# T-LOG_v1_1.net
KiCad netlist of a schematic drawn in Altium Designer
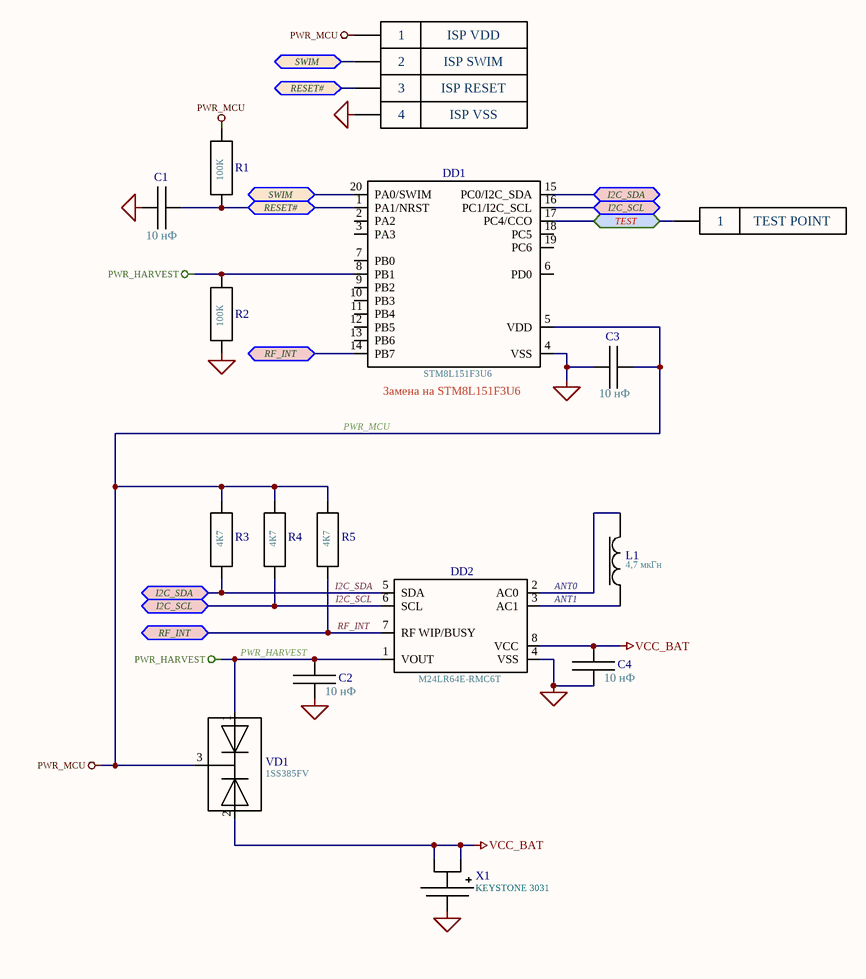
[diagram p0: T-LOG v1.1.SchDoc]

(export (version "E")
  (design (tool "Eeschema 10.0.6"))
  (components
    (comp (ref "C1")
      (value "10 нФ")
      (footprint "C0402")
      (description "Чип-конденсатор 0,01 мкФ 50 В 0402")
      (libsource (lib "RC") (part "C0402"))
    )
    (comp (ref "C2")
      (value "10 нФ")
      (footprint "C0402")
      (description "Чип-конденсатор 0,01 мкФ 50 В 0402")
      (libsource (lib "RC") (part "C0402"))
    )
    (comp (ref "C3")
      (value "10 нФ")
      (footprint "C0402")
      (description "Чип-конденсатор 0,01 мкФ 50 В 0402")
      (libsource (lib "RC") (part "C0402"))
    )
    (comp (ref "C4")
      (value "10 нФ")
      (footprint "C0402")
      (description "Чип-конденсатор 0,01 мкФ 50 В 0402")
      (libsource (lib "RC") (part "C0402"))
    )
    (comp (ref "DD1")
      (value "STM8L151F3U6")
      (footprint "UFQPN20_3x3_0.5")
      (description "Микроконтроллер  STM8L151F3U6 UFQFPN-20")
      (libsource (lib "MCU") (part "STM8L151F3U6"))
    )
    (comp (ref "DD2")
      (value "M24LR64E-RMC6T")
      (footprint "UDFN-8_2X3")
      (description "Память EEPROM I2C/NFC 64Кбит M24LR64E-RMC6T UFDFN8 ST")
      (libsource (lib "MEMORY") (part "M24LR64E-RMC6T"))
    )
    (comp (ref "K1")
      (value "ISP")
      (footprint "THRU_HOLE_02x045")
      (description "used for STM8L ISP in T-LOG project")
      (libsource (lib "CONNECTORS") (part "THRU_HOLE_02x045"))
    )
    (comp (ref "K2")
      (value "ISP")
      (footprint "THRU_HOLE_02x045")
      (description "used for STM8L ISP in T-LOG project")
      (libsource (lib "CONNECTORS") (part "THRU_HOLE_02x045"))
    )
    (comp (ref "K3")
      (value "ISP")
      (footprint "THRU_HOLE_02x045")
      (description "used for STM8L ISP in T-LOG project")
      (libsource (lib "CONNECTORS") (part "THRU_HOLE_02x045"))
    )
    (comp (ref "K4")
      (value "ISP")
      (footprint "THRU_HOLE_02x045")
      (description "used for STM8L ISP in T-LOG project")
      (libsource (lib "CONNECTORS") (part "THRU_HOLE_02x045"))
    )
    (comp (ref "K5")
      (value "TEST POINT")
      (footprint "THRU_HOLE_02x045")
      (libsource (lib "CONNECTORS") (part "THRU_HOLE_02x045"))
    )
    (comp (ref "L1")
      (value "4,7 мкГн")
      (footprint "WE-LQ_1210")
      (description "Чип-индуктивность WE-LQ 744032004 4,7 мкГн 0,49 А Wurth Elektronik")
      (libsource (lib "ZX") (part "WE-LQ_744032004"))
    )
    (comp (ref "R1")
      (value "100К")
      (footprint "R0402")
      (description "Чип-резистор 100 кОм 5% 0402")
      (libsource (lib "RC") (part "R0402"))
    )
    (comp (ref "R2")
      (value "100К")
      (footprint "R0402")
      (description "Чип-резистор 100 кОм 5% 0402")
      (libsource (lib "RC") (part "R0402"))
    )
    (comp (ref "R3")
      (value "4К7")
      (footprint "R0402")
      (description "Чип-резистор 4,7 кОм 5% 0402")
      (libsource (lib "RC") (part "R0402"))
    )
    (comp (ref "R4")
      (value "4К7")
      (footprint "R0402")
      (description "Чип-резистор 4,7 кОм 5% 0402")
      (libsource (lib "RC") (part "R0402"))
    )
    (comp (ref "R5")
      (value "4К7")
      (footprint "R0402")
      (description "Чип-резистор 4,7 кОм 5% 0402")
      (libsource (lib "RC") (part "R0402"))
    )
    (comp (ref "VD1")
      (value "1SS385FV")
      (footprint "SOT-723")
      (description "Диодная сборка с общим катодом 1SS385FV SOT-723 Toshiba")
      (libsource (lib "SEMICONDUCTORS") (part "1SS385FV"))
    )
    (comp (ref "X1")
      (value "KEYSTONE 3031")
      (footprint "KEYSTONE_3031")
      (description "Держатель элемента CR1025 KEYSTONE 3031")
      (libsource (lib "CONNECTORS") (part "KEYSTONE_3031"))
    )
  )
  (nets
    (net (code "1") (name "/ANT0") (class "Default")
      (node (ref "DD2") (pin "2") (pinfunction "AC0_2") (pintype "passive"))
      (node (ref "L1") (pin "2") (pinfunction "2_2") (pintype "passive"))
    )
    (net (code "2") (name "/ANT1") (class "Default")
      (node (ref "DD2") (pin "3") (pinfunction "AC1_3") (pintype "passive"))
      (node (ref "L1") (pin "1") (pinfunction "1_1") (pintype "passive"))
    )
    (net (code "3") (name "/I2C_SCL") (class "Default")
      (node (ref "DD1") (pin "16") (pinfunction "PC1/I2C_SCL_16") (pintype "passive"))
      (node (ref "DD2") (pin "6") (pinfunction "SCL_6") (pintype "passive"))
      (node (ref "R4") (pin "1") (pinfunction "1_1") (pintype "passive"))
    )
    (net (code "4") (name "/I2C_SDA") (class "Default")
      (node (ref "DD1") (pin "15") (pinfunction "PC0/I2C_SDA_15") (pintype "passive"))
      (node (ref "DD2") (pin "5") (pinfunction "SDA_5") (pintype "passive"))
      (node (ref "R3") (pin "1") (pinfunction "1_1") (pintype "passive"))
    )
    (net (code "5") (name "/RESET#") (class "Default")
      (node (ref "C1") (pin "2") (pinfunction "2_2") (pintype "passive"))
      (node (ref "DD1") (pin "1") (pinfunction "PA1/NRST_1") (pintype "passive"))
      (node (ref "K3") (pin "1") (pinfunction "1_1") (pintype "passive"))
      (node (ref "R1") (pin "1") (pinfunction "1_1") (pintype "passive"))
    )
    (net (code "6") (name "/RF_INT") (class "Default")
      (node (ref "DD1") (pin "14") (pinfunction "PB7_14") (pintype "passive"))
      (node (ref "DD2") (pin "7") (pinfunction "RF_WIP/BUSY_7") (pintype "passive"))
      (node (ref "R5") (pin "1") (pinfunction "1_1") (pintype "passive"))
    )
    (net (code "7") (name "/SWIM") (class "Default")
      (node (ref "DD1") (pin "20") (pinfunction "PA0/SWIM_20") (pintype "passive"))
      (node (ref "K2") (pin "1") (pinfunction "1_1") (pintype "passive"))
    )
    (net (code "8") (name "/TEST") (class "Default")
      (node (ref "DD1") (pin "17") (pinfunction "PC4/CCO_17") (pintype "passive"))
      (node (ref "K5") (pin "1") (pinfunction "1_1") (pintype "passive"))
    )
    (net (code "9") (name "GND") (class "Default")
      (node (ref "C1") (pin "1") (pinfunction "1_1") (pintype "passive"))
      (node (ref "C2") (pin "1") (pinfunction "1_1") (pintype "passive"))
      (node (ref "C3") (pin "2") (pinfunction "2_2") (pintype "passive"))
      (node (ref "C4") (pin "1") (pinfunction "1_1") (pintype "passive"))
      (node (ref "DD1") (pin "4") (pinfunction "VSS_4") (pintype "passive"))
      (node (ref "DD2") (pin "4") (pinfunction "VSS_4") (pintype "passive"))
      (node (ref "K4") (pin "1") (pinfunction "1_1") (pintype "passive"))
      (node (ref "R2") (pin "1") (pinfunction "1_1") (pintype "passive"))
      (node (ref "X1") (pin "3") (pinfunction "3_3") (pintype "passive"))
    )
    (net (code "10") (name "PWR_HARVEST") (class "Default")
      (node (ref "C2") (pin "2") (pinfunction "2_2") (pintype "passive"))
      (node (ref "DD1") (pin "8") (pinfunction "PB1_8") (pintype "passive"))
      (node (ref "DD2") (pin "1") (pinfunction "VOUT_1") (pintype "passive"))
      (node (ref "R2") (pin "2") (pinfunction "2_2") (pintype "passive"))
      (node (ref "VD1") (pin "1") (pinfunction "1_1") (pintype "passive"))
    )
    (net (code "11") (name "PWR_MCU") (class "Default")
      (node (ref "C3") (pin "1") (pinfunction "1_1") (pintype "passive"))
      (node (ref "DD1") (pin "5") (pinfunction "VDD_5") (pintype "passive"))
      (node (ref "K1") (pin "1") (pinfunction "1_1") (pintype "passive"))
      (node (ref "R1") (pin "2") (pinfunction "2_2") (pintype "passive"))
      (node (ref "R3") (pin "2") (pinfunction "2_2") (pintype "passive"))
      (node (ref "R4") (pin "2") (pinfunction "2_2") (pintype "passive"))
      (node (ref "R5") (pin "2") (pinfunction "2_2") (pintype "passive"))
      (node (ref "VD1") (pin "3") (pinfunction "3_3") (pintype "passive"))
    )
    (net (code "12") (name "VCC_BAT") (class "Default")
      (node (ref "C4") (pin "2") (pinfunction "2_2") (pintype "passive"))
      (node (ref "DD2") (pin "8") (pinfunction "VCC_8") (pintype "passive"))
      (node (ref "VD1") (pin "2") (pinfunction "2_2") (pintype "passive"))
      (node (ref "X1") (pin "1") (pinfunction "1_1") (pintype "passive"))
      (node (ref "X1") (pin "2") (pinfunction "2_2") (pintype "passive"))
    )
    (net (code "13") (name "unconnected-(DD1-PA2-Pad2)") (class "Default")
      (node (ref "DD1") (pin "2") (pinfunction "PA2_2") (pintype "passive"))
    )
    (net (code "14") (name "unconnected-(DD1-PA3-Pad3)") (class "Default")
      (node (ref "DD1") (pin "3") (pinfunction "PA3_3") (pintype "passive"))
    )
    (net (code "15") (name "unconnected-(DD1-PB0-Pad7)") (class "Default")
      (node (ref "DD1") (pin "7") (pinfunction "PB0_7") (pintype "passive"))
    )
    (net (code "16") (name "unconnected-(DD1-PB2-Pad9)") (class "Default")
      (node (ref "DD1") (pin "9") (pinfunction "PB2_9") (pintype "passive"))
    )
    (net (code "17") (name "unconnected-(DD1-PB3-Pad10)") (class "Default")
      (node (ref "DD1") (pin "10") (pinfunction "PB3_10") (pintype "passive"))
    )
    (net (code "18") (name "unconnected-(DD1-PB4-Pad11)") (class "Default")
      (node (ref "DD1") (pin "11") (pinfunction "PB4_11") (pintype "passive"))
    )
    (net (code "19") (name "unconnected-(DD1-PB5-Pad12)") (class "Default")
      (node (ref "DD1") (pin "12") (pinfunction "PB5_12") (pintype "passive"))
    )
    (net (code "20") (name "unconnected-(DD1-PB6-Pad13)") (class "Default")
      (node (ref "DD1") (pin "13") (pinfunction "PB6_13") (pintype "passive"))
    )
    (net (code "21") (name "unconnected-(DD1-PC5-Pad18)") (class "Default")
      (node (ref "DD1") (pin "18") (pinfunction "PC5_18") (pintype "passive"))
    )
    (net (code "22") (name "unconnected-(DD1-PC6-Pad19)") (class "Default")
      (node (ref "DD1") (pin "19") (pinfunction "PC6_19") (pintype "passive"))
    )
    (net (code "23") (name "unconnected-(DD1-PD0-Pad6)") (class "Default")
      (node (ref "DD1") (pin "6") (pinfunction "PD0_6") (pintype "passive"))
    )
  )
)
